# Tact_Switch.net
KiCad netlist of a schematic drawn in EAGLE
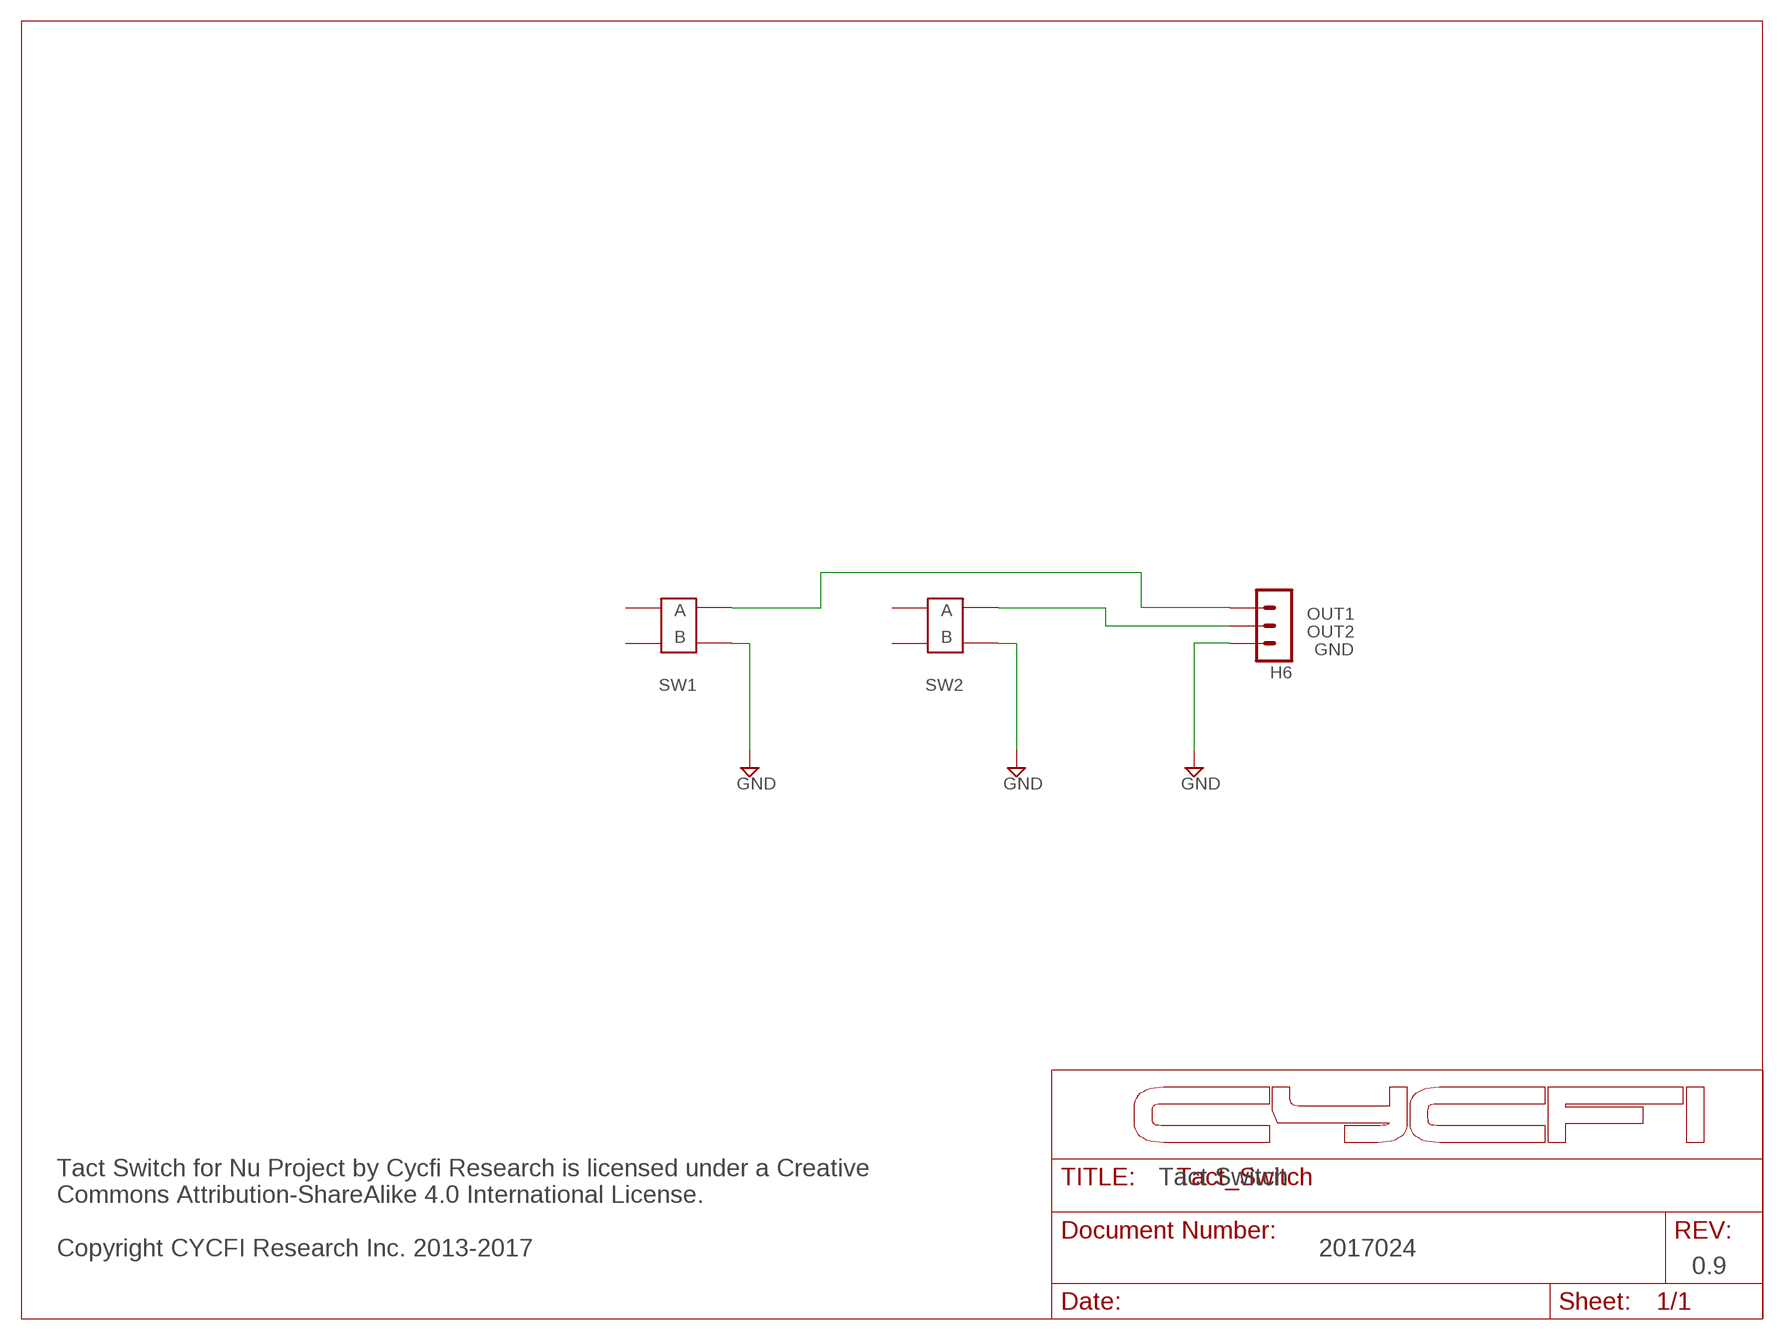
[diagram p0: schematic, sheet 1]

(export (version "E")
  (design (tool "Eeschema 10.0.6"))
  (components
    (comp (ref "H6")
      (value "3PIN-SMD-2.54MM")
      (footprint "eagle-import:3P-SMD-2.54MM")
      (libsource (lib "eagle-import") (part "3PIN-SMD-2.54MM"))
    )
    (comp (ref "U$1")
      (value "TACT_MJTP1230")
      (footprint "eagle-import:MJTP1230")
      (libsource (lib "eagle-import") (part "TACT_MJTP1230"))
    )
    (comp (ref "U$2")
      (value "TACT_MJTP1230")
      (footprint "eagle-import:MJTP1230")
      (libsource (lib "eagle-import") (part "TACT_MJTP1230"))
    )
  )
  (nets
    (net (code "1") (name "GND") (class "Default")
      (node (ref "H6") (pin "P$3") (pinfunction "3_P$3") (pintype "passive"))
      (node (ref "U$1") (pin "2B") (pinfunction "P2B_2B") (pintype "bidirectional"))
      (node (ref "U$2") (pin "2B") (pinfunction "P2B_2B") (pintype "bidirectional"))
    )
    (net (code "2") (name "Net-(H6-1)") (class "Default")
      (node (ref "H6") (pin "P$1") (pinfunction "1_P$1") (pintype "passive"))
      (node (ref "U$1") (pin "1B") (pinfunction "P1B_1B") (pintype "bidirectional"))
    )
    (net (code "3") (name "Net-(H6-2)") (class "Default")
      (node (ref "H6") (pin "P$2") (pinfunction "2_P$2") (pintype "passive"))
      (node (ref "U$2") (pin "1B") (pinfunction "P1B_1B") (pintype "bidirectional"))
    )
    (net (code "4") (name "unconnected-(U$1-P1A-Pad1A)") (class "Default")
      (node (ref "U$1") (pin "1A") (pinfunction "P1A_1A") (pintype "bidirectional"))
    )
    (net (code "5") (name "unconnected-(U$1-P2A-Pad2A)") (class "Default")
      (node (ref "U$1") (pin "2A") (pinfunction "P2A_2A") (pintype "bidirectional"))
    )
    (net (code "6") (name "unconnected-(U$2-P1A-Pad1A)") (class "Default")
      (node (ref "U$2") (pin "1A") (pinfunction "P1A_1A") (pintype "bidirectional"))
    )
    (net (code "7") (name "unconnected-(U$2-P2A-Pad2A)") (class "Default")
      (node (ref "U$2") (pin "2A") (pinfunction "P2A_2A") (pintype "bidirectional"))
    )
  )
)
